# ArdWifi.net
KiCad netlist of a schematic drawn in EAGLE
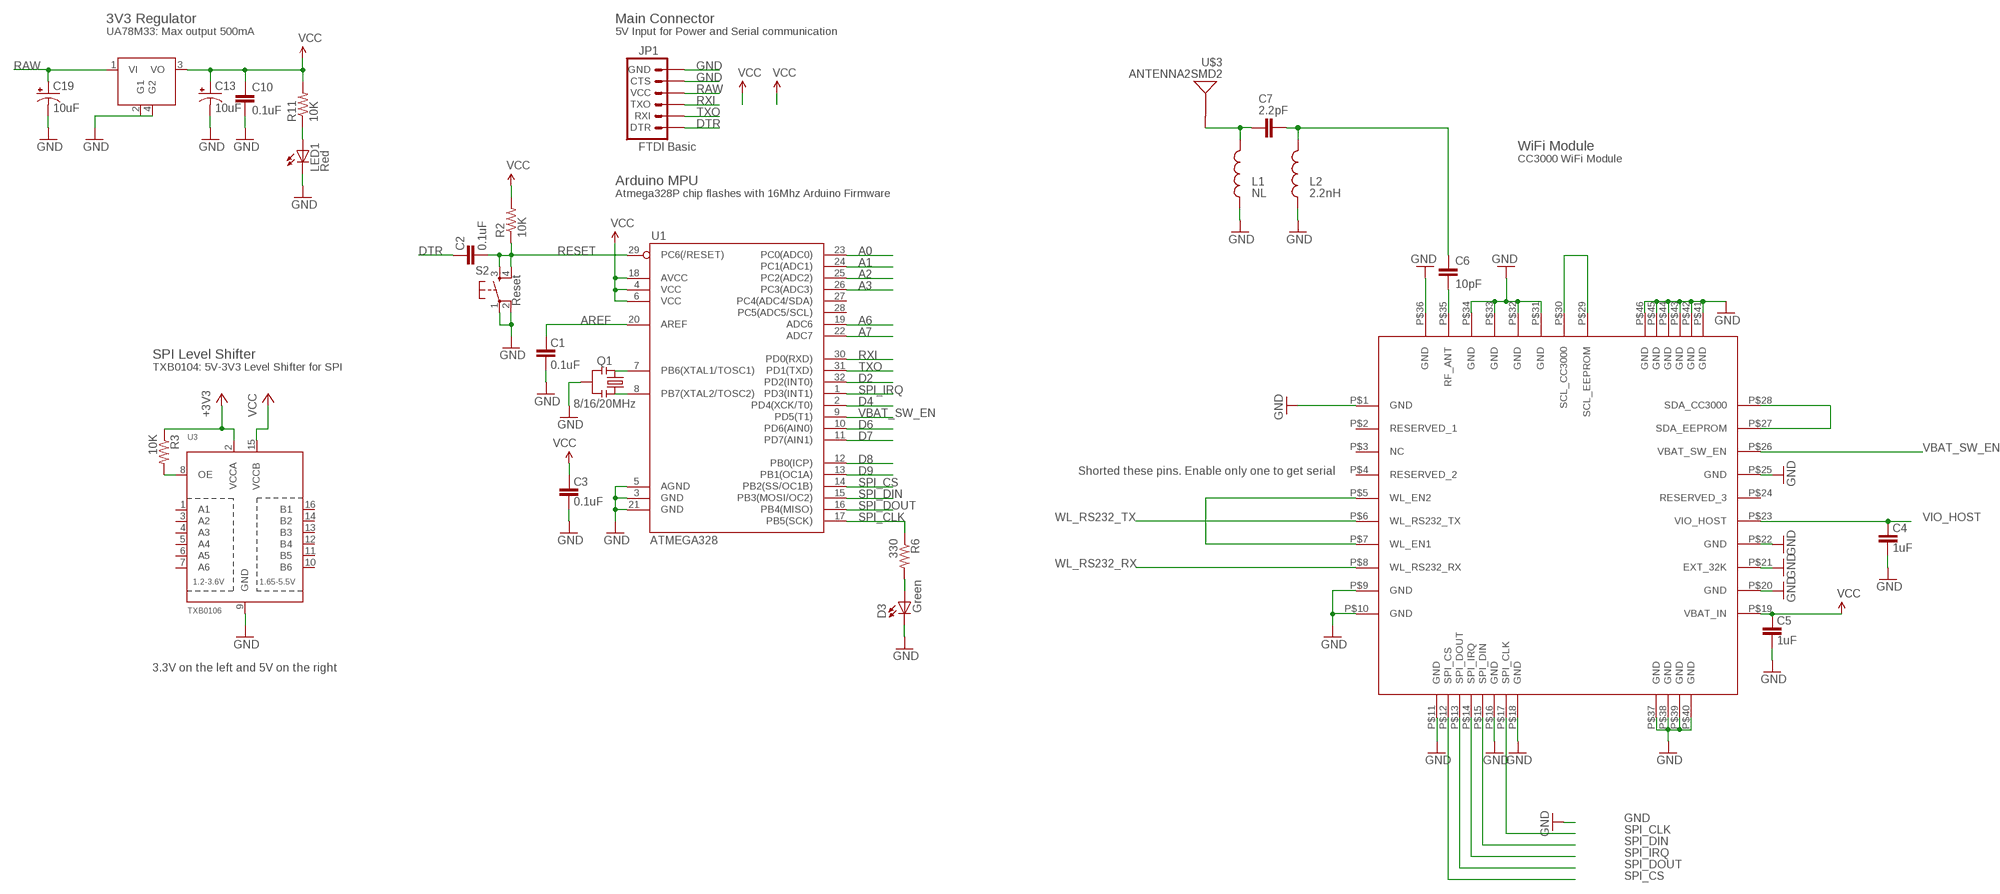
[diagram p0: schematic, sheet 1]

(export (version "E")
  (design (tool "Eeschema 10.0.6"))
  (components
    (comp (ref "C1")
      (value "0.1uF")
      (footprint "eagle-import:0402-CAP")
      (libsource (lib "eagle-import") (part "CAP0402-CAP"))
    )
    (comp (ref "C2")
      (value "0.1uF")
      (footprint "eagle-import:0402-CAP")
      (libsource (lib "eagle-import") (part "CAP0402-CAP"))
    )
    (comp (ref "C3")
      (value "0.1uF")
      (footprint "eagle-import:0402-CAP")
      (libsource (lib "eagle-import") (part "CAP0402-CAP"))
    )
    (comp (ref "C4")
      (value "1uF")
      (footprint "eagle-import:0402-CAP")
      (libsource (lib "eagle-import") (part "CAP0402-CAP"))
    )
    (comp (ref "C5")
      (value "1uF")
      (footprint "eagle-import:0402-CAP")
      (libsource (lib "eagle-import") (part "CAP0402-CAP"))
    )
    (comp (ref "C6")
      (value "10pF")
      (footprint "eagle-import:0402-CAP")
      (libsource (lib "eagle-import") (part "CAP0402-CAP"))
    )
    (comp (ref "C7")
      (value "2.2pF")
      (footprint "eagle-import:0402-CAP")
      (libsource (lib "eagle-import") (part "CAP0402-CAP"))
    )
    (comp (ref "C10")
      (value "0.1uF")
      (footprint "eagle-import:0402-CAP")
      (libsource (lib "eagle-import") (part "CAP0402-CAP"))
    )
    (comp (ref "C13")
      (value "10uF")
      (footprint "eagle-import:EIA3216")
      (libsource (lib "eagle-import") (part "CAP_POL1206"))
    )
    (comp (ref "C19")
      (value "10uF")
      (footprint "eagle-import:EIA3216")
      (libsource (lib "eagle-import") (part "CAP_POL1206"))
    )
    (comp (ref "D3")
      (value "Green")
      (footprint "eagle-import:LED-0603")
      (libsource (lib "eagle-import") (part "LED0603"))
    )
    (comp (ref "JP1")
      (value "FTDI Basic")
      (footprint "eagle-import:1X06")
      (libsource (lib "eagle-import") (part "ARDUINO_SERIAL_PROGRAMPTH"))
    )
    (comp (ref "L1")
      (value "NL")
      (footprint "eagle-import:C0402")
      (libsource (lib "eagle-import") (part "INDUCTOR0402"))
    )
    (comp (ref "L2")
      (value "2.2nH")
      (footprint "eagle-import:C0402")
      (libsource (lib "eagle-import") (part "INDUCTOR0402"))
    )
    (comp (ref "LED1")
      (value "Red")
      (footprint "eagle-import:LED-0603")
      (libsource (lib "eagle-import") (part "LED0603"))
    )
    (comp (ref "Q1")
      (value "8/16/20MHz")
      (footprint "eagle-import:RESONATOR-SMD")
      (libsource (lib "eagle-import") (part "RESONATORSMD"))
    )
    (comp (ref "R2")
      (value "10K")
      (footprint "eagle-import:0402-RES")
      (libsource (lib "eagle-import") (part "RESISTOR0402-RES"))
    )
    (comp (ref "R3")
      (value "10K")
      (footprint "eagle-import:R0603")
      (libsource (lib "eagle-import") (part "R-US_R0603"))
    )
    (comp (ref "R6")
      (value "330")
      (footprint "eagle-import:0402-RES")
      (libsource (lib "eagle-import") (part "RESISTOR0402-RES"))
    )
    (comp (ref "R11")
      (value "10K")
      (footprint "eagle-import:0402-RES")
      (libsource (lib "eagle-import") (part "RESISTOR0402-RES"))
    )
    (comp (ref "REG1")
      (value "LDO_UA78M33")
      (footprint "eagle-import:SOT223")
      (libsource (lib "eagle-import") (part "LDO_UA78M33"))
    )
    (comp (ref "S2")
      (value "Reset")
      (footprint "eagle-import:TACTILE_SWITCH_SMD")
      (libsource (lib "eagle-import") (part "TAC_SWITCHSMD"))
    )
    (comp (ref "U$1")
      (value "CC3000")
      (footprint "eagle-import:CC3000")
      (fields (field (name "AUTHOR") "Matt Bigarani"))
      (libsource (lib "eagle-import") (part "CC3000"))
    )
    (comp (ref "U$3")
      (value "ANTENNA2SMD2")
      (footprint "eagle-import:ANTENNA-CHIP3")
      (libsource (lib "eagle-import") (part "ANTENNA2SMD2"))
    )
    (comp (ref "U1")
      (value "ATMEGA328")
      (footprint "eagle-import:TQFP32-08")
      (libsource (lib "eagle-import") (part "ATMEGA168"))
    )
    (comp (ref "U3")
      (value "TXB0106")
      (footprint "eagle-import:TSSOP16")
      (libsource (lib "eagle-import") (part "TXB0106PWR"))
    )
  )
  (nets
    (net (code "1") (name "+3V3") (class "Default")
      (node (ref "R3") (pin "1") (pinfunction "1_1") (pintype "passive"))
      (node (ref "U3") (pin "2") (pinfunction "VCCA_2") (pintype "bidirectional"))
    )
    (net (code "2") (name "/A0") (class "Default")
      (node (ref "U1") (pin "23") (pinfunction "PC0(ADC0)_23") (pintype "bidirectional"))
    )
    (net (code "3") (name "/A1") (class "Default")
      (node (ref "U1") (pin "24") (pinfunction "PC1(ADC1)_24") (pintype "bidirectional"))
    )
    (net (code "4") (name "/A2") (class "Default")
      (node (ref "U1") (pin "25") (pinfunction "PC2(ADC2)_25") (pintype "bidirectional"))
    )
    (net (code "5") (name "/A3") (class "Default")
      (node (ref "U1") (pin "26") (pinfunction "PC3(ADC3)_26") (pintype "bidirectional"))
    )
    (net (code "6") (name "/A6") (class "Default")
      (node (ref "U1") (pin "19") (pinfunction "ADC6_19") (pintype "bidirectional"))
    )
    (net (code "7") (name "/A7") (class "Default")
      (node (ref "U1") (pin "22") (pinfunction "ADC7_22") (pintype "bidirectional"))
    )
    (net (code "8") (name "/AREF") (class "Default")
      (node (ref "C1") (pin "2") (pinfunction "2_2") (pintype "passive"))
      (node (ref "U1") (pin "20") (pinfunction "AREF_20") (pintype "bidirectional"))
    )
    (net (code "9") (name "/D2") (class "Default")
      (node (ref "U1") (pin "32") (pinfunction "PD2(INT0)_32") (pintype "bidirectional"))
    )
    (net (code "10") (name "/D4") (class "Default")
      (node (ref "U1") (pin "2") (pinfunction "PD4(XCK/T0)_2") (pintype "bidirectional"))
    )
    (net (code "11") (name "/D6") (class "Default")
      (node (ref "U1") (pin "10") (pinfunction "PD6(AIN0)_10") (pintype "bidirectional"))
    )
    (net (code "12") (name "/D7") (class "Default")
      (node (ref "U1") (pin "11") (pinfunction "PD7(AIN1)_11") (pintype "bidirectional"))
    )
    (net (code "13") (name "/D8") (class "Default")
      (node (ref "U1") (pin "12") (pinfunction "PB0(ICP)_12") (pintype "bidirectional"))
    )
    (net (code "14") (name "/D9") (class "Default")
      (node (ref "U1") (pin "13") (pinfunction "PB1(OC1A)_13") (pintype "bidirectional"))
    )
    (net (code "15") (name "/DTR") (class "Default")
      (node (ref "C2") (pin "2") (pinfunction "2_2") (pintype "passive"))
      (node (ref "JP1") (pin "1") (pinfunction "DTR_1") (pintype "passive"))
    )
    (net (code "16") (name "/RAW") (class "Default")
      (node (ref "C19") (pin "A") (pinfunction "+_A") (pintype "passive"))
      (node (ref "JP1") (pin "4") (pinfunction "VCC_4") (pintype "passive"))
      (node (ref "REG1") (pin "1") (pinfunction "VI_1") (pintype "bidirectional"))
    )
    (net (code "17") (name "/RESET") (class "Default")
      (node (ref "C2") (pin "1") (pinfunction "1_1") (pintype "passive"))
      (node (ref "R2") (pin "1") (pinfunction "1_1") (pintype "passive"))
      (node (ref "S2") (pin "3") (pinfunction "3_3") (pintype "passive"))
      (node (ref "S2") (pin "4") (pinfunction "4_4") (pintype "passive"))
      (node (ref "U1") (pin "29") (pinfunction "PC6(/RESET)_29") (pintype "bidirectional"))
    )
    (net (code "18") (name "/RXI") (class "Default")
      (node (ref "JP1") (pin "3") (pinfunction "TXO_3") (pintype "passive"))
      (node (ref "U1") (pin "30") (pinfunction "PD0(RXD)_30") (pintype "bidirectional"))
    )
    (net (code "19") (name "/SPI_CLK") (class "Default")
      (node (ref "R6") (pin "1") (pinfunction "1_1") (pintype "passive"))
      (node (ref "U$1") (pin "P$17") (pinfunction "SPI_CLK_P$17") (pintype "bidirectional"))
      (node (ref "U1") (pin "17") (pinfunction "PB5(SCK)_17") (pintype "bidirectional"))
    )
    (net (code "20") (name "/SPI_CS") (class "Default")
      (node (ref "U$1") (pin "P$12") (pinfunction "SPI_CS_P$12") (pintype "bidirectional"))
      (node (ref "U1") (pin "14") (pinfunction "PB2(SS/OC1B)_14") (pintype "bidirectional"))
    )
    (net (code "21") (name "/SPI_DIN") (class "Default")
      (node (ref "U$1") (pin "P$15") (pinfunction "SPI_DIN_P$15") (pintype "bidirectional"))
      (node (ref "U1") (pin "15") (pinfunction "PB3(MOSI/OC2)_15") (pintype "bidirectional"))
    )
    (net (code "22") (name "/SPI_DOUT") (class "Default")
      (node (ref "U$1") (pin "P$13") (pinfunction "SPI_DOUT_P$13") (pintype "bidirectional"))
      (node (ref "U1") (pin "16") (pinfunction "PB4(MISO)_16") (pintype "bidirectional"))
    )
    (net (code "23") (name "/SPI_IRQ") (class "Default")
      (node (ref "U$1") (pin "P$14") (pinfunction "SPI_IRQ_P$14") (pintype "bidirectional"))
      (node (ref "U1") (pin "1") (pinfunction "PD3(INT1)_1") (pintype "bidirectional"))
    )
    (net (code "24") (name "/TXO") (class "Default")
      (node (ref "JP1") (pin "2") (pinfunction "RXI_2") (pintype "passive"))
      (node (ref "U1") (pin "31") (pinfunction "PD1(TXD)_31") (pintype "bidirectional"))
    )
    (net (code "25") (name "/VBAT_SW_EN") (class "Default")
      (node (ref "U$1") (pin "P$26") (pinfunction "VBAT_SW_EN_P$26") (pintype "bidirectional"))
      (node (ref "U1") (pin "9") (pinfunction "PD5(T1)_9") (pintype "bidirectional"))
    )
    (net (code "26") (name "/VIO_HOST") (class "Default")
      (node (ref "C4") (pin "2") (pinfunction "2_2") (pintype "passive"))
      (node (ref "U$1") (pin "P$23") (pinfunction "VIO_HOST_P$23") (pintype "bidirectional"))
    )
    (net (code "27") (name "/WL_RS232_RX") (class "Default")
      (node (ref "U$1") (pin "P$8") (pinfunction "WL_RS232_RX_P$8") (pintype "bidirectional"))
    )
    (net (code "28") (name "/WL_RS232_TX") (class "Default")
      (node (ref "U$1") (pin "P$6") (pinfunction "WL_RS232_TX_P$6") (pintype "bidirectional"))
    )
    (net (code "29") (name "GND") (class "Default")
      (node (ref "C1") (pin "1") (pinfunction "1_1") (pintype "passive"))
      (node (ref "C10") (pin "2") (pinfunction "2_2") (pintype "passive"))
      (node (ref "C13") (pin "C") (pinfunction "-_C") (pintype "passive"))
      (node (ref "C19") (pin "C") (pinfunction "-_C") (pintype "passive"))
      (node (ref "C3") (pin "1") (pinfunction "1_1") (pintype "passive"))
      (node (ref "C4") (pin "1") (pinfunction "1_1") (pintype "passive"))
      (node (ref "C5") (pin "1") (pinfunction "1_1") (pintype "passive"))
      (node (ref "D3") (pin "C") (pinfunction "C_C") (pintype "passive"))
      (node (ref "JP1") (pin "5") (pinfunction "CTS_5") (pintype "passive"))
      (node (ref "JP1") (pin "6") (pinfunction "GND_6") (pintype "passive"))
      (node (ref "L1") (pin "1") (pinfunction "1_1") (pintype "passive"))
      (node (ref "L2") (pin "1") (pinfunction "1_1") (pintype "passive"))
      (node (ref "LED1") (pin "C") (pinfunction "C_C") (pintype "passive"))
      (node (ref "Q1") (pin "2") (pinfunction "2_2") (pintype "passive"))
      (node (ref "REG1") (pin "2") (pinfunction "G1_2") (pintype "bidirectional"))
      (node (ref "REG1") (pin "4") (pinfunction "G2_4") (pintype "bidirectional"))
      (node (ref "S2") (pin "1") (pinfunction "1_1") (pintype "passive"))
      (node (ref "S2") (pin "2") (pinfunction "2_2") (pintype "passive"))
      (node (ref "U$1") (pin "P$1") (pinfunction "GND_P$1") (pintype "power_in"))
      (node (ref "U$1") (pin "P$10") (pinfunction "GND_P$10") (pintype "power_in"))
      (node (ref "U$1") (pin "P$11") (pinfunction "GND_P$11") (pintype "power_in"))
      (node (ref "U$1") (pin "P$16") (pinfunction "GND_P$16") (pintype "power_in"))
      (node (ref "U$1") (pin "P$18") (pinfunction "GND_P$18") (pintype "power_in"))
      (node (ref "U$1") (pin "P$20") (pinfunction "GND_P$20") (pintype "bidirectional"))
      (node (ref "U$1") (pin "P$21") (pinfunction "EXT_32K_P$21") (pintype "bidirectional"))
      (node (ref "U$1") (pin "P$22") (pinfunction "GND_P$22") (pintype "bidirectional"))
      (node (ref "U$1") (pin "P$25") (pinfunction "GND_P$25") (pintype "bidirectional"))
      (node (ref "U$1") (pin "P$31") (pinfunction "GND_P$31") (pintype "power_in"))
      (node (ref "U$1") (pin "P$32") (pinfunction "GND_P$32") (pintype "power_in"))
      (node (ref "U$1") (pin "P$33") (pinfunction "GND_P$33") (pintype "power_in"))
      (node (ref "U$1") (pin "P$34") (pinfunction "GND_P$34") (pintype "power_in"))
      (node (ref "U$1") (pin "P$36") (pinfunction "GND_P$36") (pintype "passive"))
      (node (ref "U$1") (pin "P$37") (pinfunction "GND_P$37") (pintype "power_in"))
      (node (ref "U$1") (pin "P$38") (pinfunction "GND_P$38") (pintype "passive"))
      (node (ref "U$1") (pin "P$39") (pinfunction "GND_P$39") (pintype "power_in"))
      (node (ref "U$1") (pin "P$40") (pinfunction "GND_P$40") (pintype "power_in"))
      (node (ref "U$1") (pin "P$41") (pinfunction "GND_P$41") (pintype "power_in"))
      (node (ref "U$1") (pin "P$42") (pinfunction "GND_P$42") (pintype "power_in"))
      (node (ref "U$1") (pin "P$43") (pinfunction "GND_P$43") (pintype "power_in"))
      (node (ref "U$1") (pin "P$44") (pinfunction "GND_P$44") (pintype "power_in"))
      (node (ref "U$1") (pin "P$45") (pinfunction "GND_P$45") (pintype "power_in"))
      (node (ref "U$1") (pin "P$46") (pinfunction "GND_P$46") (pintype "power_in"))
      (node (ref "U$1") (pin "P$9") (pinfunction "GND_P$9") (pintype "bidirectional"))
      (node (ref "U1") (pin "21") (pinfunction "GND_21") (pintype "bidirectional"))
      (node (ref "U1") (pin "3") (pinfunction "GND_3") (pintype "bidirectional"))
      (node (ref "U1") (pin "5") (pinfunction "AGND_5") (pintype "bidirectional"))
      (node (ref "U3") (pin "9") (pinfunction "GND_9") (pintype "bidirectional"))
    )
    (net (code "30") (name "Net-(C6-Pad1)") (class "Default")
      (node (ref "C6") (pin "1") (pinfunction "1_1") (pintype "passive"))
      (node (ref "C7") (pin "2") (pinfunction "2_2") (pintype "passive"))
      (node (ref "L2") (pin "2") (pinfunction "2_2") (pintype "passive"))
    )
    (net (code "31") (name "Net-(D3-PadA)") (class "Default")
      (node (ref "D3") (pin "A") (pinfunction "A_A") (pintype "passive"))
      (node (ref "R6") (pin "2") (pinfunction "2_2") (pintype "passive"))
    )
    (net (code "32") (name "Net-(LED1-PadA)") (class "Default")
      (node (ref "LED1") (pin "A") (pinfunction "A_A") (pintype "passive"))
      (node (ref "R11") (pin "1") (pinfunction "1_1") (pintype "passive"))
    )
    (net (code "33") (name "Net-(U$1-RF_ANT)") (class "Default")
      (node (ref "C6") (pin "2") (pinfunction "2_2") (pintype "passive"))
      (node (ref "U$1") (pin "P$35") (pinfunction "RF_ANT_P$35") (pintype "bidirectional"))
    )
    (net (code "34") (name "Net-(U$1-SCL_CC3000)") (class "Default")
      (node (ref "U$1") (pin "P$29") (pinfunction "SCL_EEPROM_P$29") (pintype "power_in"))
      (node (ref "U$1") (pin "P$30") (pinfunction "SCL_CC3000_P$30") (pintype "power_in"))
    )
    (net (code "35") (name "Net-(U$1-SDA_CC3000)") (class "Default")
      (node (ref "U$1") (pin "P$27") (pinfunction "SDA_EEPROM_P$27") (pintype "bidirectional"))
      (node (ref "U$1") (pin "P$28") (pinfunction "SDA_CC3000_P$28") (pintype "bidirectional"))
    )
    (net (code "36") (name "Net-(U$1-WL_EN1)") (class "Default")
      (node (ref "U$1") (pin "P$5") (pinfunction "WL_EN2_P$5") (pintype "bidirectional"))
      (node (ref "U$1") (pin "P$7") (pinfunction "WL_EN1_P$7") (pintype "bidirectional"))
    )
    (net (code "37") (name "Net-(U$3-SIGNAL)") (class "Default")
      (node (ref "C7") (pin "1") (pinfunction "1_1") (pintype "passive"))
      (node (ref "L1") (pin "2") (pinfunction "2_2") (pintype "passive"))
      (node (ref "U$3") (pin "FEED") (pinfunction "SIGNAL_FEED") (pintype "bidirectional"))
    )
    (net (code "38") (name "Net-(U1-PB6(XTAL1{slash}TOSC1))") (class "Default")
      (node (ref "Q1") (pin "3") (pinfunction "3_3") (pintype "passive"))
      (node (ref "U1") (pin "7") (pinfunction "PB6(XTAL1/TOSC1)_7") (pintype "bidirectional"))
    )
    (net (code "39") (name "Net-(U1-PB7(XTAL2{slash}TOSC2))") (class "Default")
      (node (ref "Q1") (pin "1") (pinfunction "1_1") (pintype "passive"))
      (node (ref "U1") (pin "8") (pinfunction "PB7(XTAL2/TOSC2)_8") (pintype "bidirectional"))
    )
    (net (code "40") (name "Net-(U3-OE)") (class "Default")
      (node (ref "R3") (pin "2") (pinfunction "2_2") (pintype "passive"))
      (node (ref "U3") (pin "8") (pinfunction "OE_8") (pintype "bidirectional"))
    )
    (net (code "41") (name "VCC") (class "Default")
      (node (ref "C10") (pin "1") (pinfunction "1_1") (pintype "passive"))
      (node (ref "C13") (pin "A") (pinfunction "+_A") (pintype "passive"))
      (node (ref "C3") (pin "2") (pinfunction "2_2") (pintype "passive"))
      (node (ref "C5") (pin "2") (pinfunction "2_2") (pintype "passive"))
      (node (ref "R11") (pin "2") (pinfunction "2_2") (pintype "passive"))
      (node (ref "R2") (pin "2") (pinfunction "2_2") (pintype "passive"))
      (node (ref "REG1") (pin "3") (pinfunction "VO_3") (pintype "bidirectional"))
      (node (ref "U$1") (pin "P$19") (pinfunction "VBAT_IN_P$19") (pintype "bidirectional"))
      (node (ref "U1") (pin "18") (pinfunction "AVCC_18") (pintype "bidirectional"))
      (node (ref "U1") (pin "4") (pinfunction "VCC_4") (pintype "bidirectional"))
      (node (ref "U1") (pin "6") (pinfunction "VCC_6") (pintype "bidirectional"))
      (node (ref "U3") (pin "15") (pinfunction "VCCB_15") (pintype "bidirectional"))
    )
    (net (code "42") (name "unconnected-(U$1-NC-PadP$3)") (class "Default")
      (node (ref "U$1") (pin "P$3") (pinfunction "NC_P$3") (pintype "no_connect"))
    )
    (net (code "43") (name "unconnected-(U$1-RESERVED_1-PadP$2)") (class "Default")
      (node (ref "U$1") (pin "P$2") (pinfunction "RESERVED_1_P$2") (pintype "bidirectional"))
    )
    (net (code "44") (name "unconnected-(U$1-RESERVED_2-PadP$4)") (class "Default")
      (node (ref "U$1") (pin "P$4") (pinfunction "RESERVED_2_P$4") (pintype "bidirectional"))
    )
    (net (code "45") (name "unconnected-(U$1-RESERVED_3-PadP$24)") (class "Default")
      (node (ref "U$1") (pin "P$24") (pinfunction "RESERVED_3_P$24") (pintype "bidirectional"))
    )
    (net (code "46") (name "unconnected-(U1-PC4(ADC4{slash}SDA)-Pad27)") (class "Default")
      (node (ref "U1") (pin "27") (pinfunction "PC4(ADC4/SDA)_27") (pintype "bidirectional"))
    )
    (net (code "47") (name "unconnected-(U1-PC5(ADC5{slash}SCL)-Pad28)") (class "Default")
      (node (ref "U1") (pin "28") (pinfunction "PC5(ADC5/SCL)_28") (pintype "bidirectional"))
    )
    (net (code "48") (name "unconnected-(U3-A1-Pad1)") (class "Default")
      (node (ref "U3") (pin "1") (pinfunction "A1_1") (pintype "bidirectional"))
    )
    (net (code "49") (name "unconnected-(U3-A2-Pad3)") (class "Default")
      (node (ref "U3") (pin "3") (pinfunction "A2_3") (pintype "bidirectional"))
    )
    (net (code "50") (name "unconnected-(U3-A3-Pad4)") (class "Default")
      (node (ref "U3") (pin "4") (pinfunction "A3_4") (pintype "bidirectional"))
    )
    (net (code "51") (name "unconnected-(U3-A4-Pad5)") (class "Default")
      (node (ref "U3") (pin "5") (pinfunction "A4_5") (pintype "bidirectional"))
    )
    (net (code "52") (name "unconnected-(U3-A5-Pad6)") (class "Default")
      (node (ref "U3") (pin "6") (pinfunction "A5_6") (pintype "bidirectional"))
    )
    (net (code "53") (name "unconnected-(U3-A6-Pad7)") (class "Default")
      (node (ref "U3") (pin "7") (pinfunction "A6_7") (pintype "bidirectional"))
    )
    (net (code "54") (name "unconnected-(U3-B1-Pad16)") (class "Default")
      (node (ref "U3") (pin "16") (pinfunction "B1_16") (pintype "bidirectional"))
    )
    (net (code "55") (name "unconnected-(U3-B2-Pad14)") (class "Default")
      (node (ref "U3") (pin "14") (pinfunction "B2_14") (pintype "bidirectional"))
    )
    (net (code "56") (name "unconnected-(U3-B3-Pad13)") (class "Default")
      (node (ref "U3") (pin "13") (pinfunction "B3_13") (pintype "bidirectional"))
    )
    (net (code "57") (name "unconnected-(U3-B4-Pad12)") (class "Default")
      (node (ref "U3") (pin "12") (pinfunction "B4_12") (pintype "bidirectional"))
    )
    (net (code "58") (name "unconnected-(U3-B5-Pad11)") (class "Default")
      (node (ref "U3") (pin "11") (pinfunction "B5_11") (pintype "bidirectional"))
    )
    (net (code "59") (name "unconnected-(U3-B6-Pad10)") (class "Default")
      (node (ref "U3") (pin "10") (pinfunction "B6_10") (pintype "bidirectional"))
    )
  )
)
